# schematic.net
KiCad netlist of a schematic drawn in EasyEDA
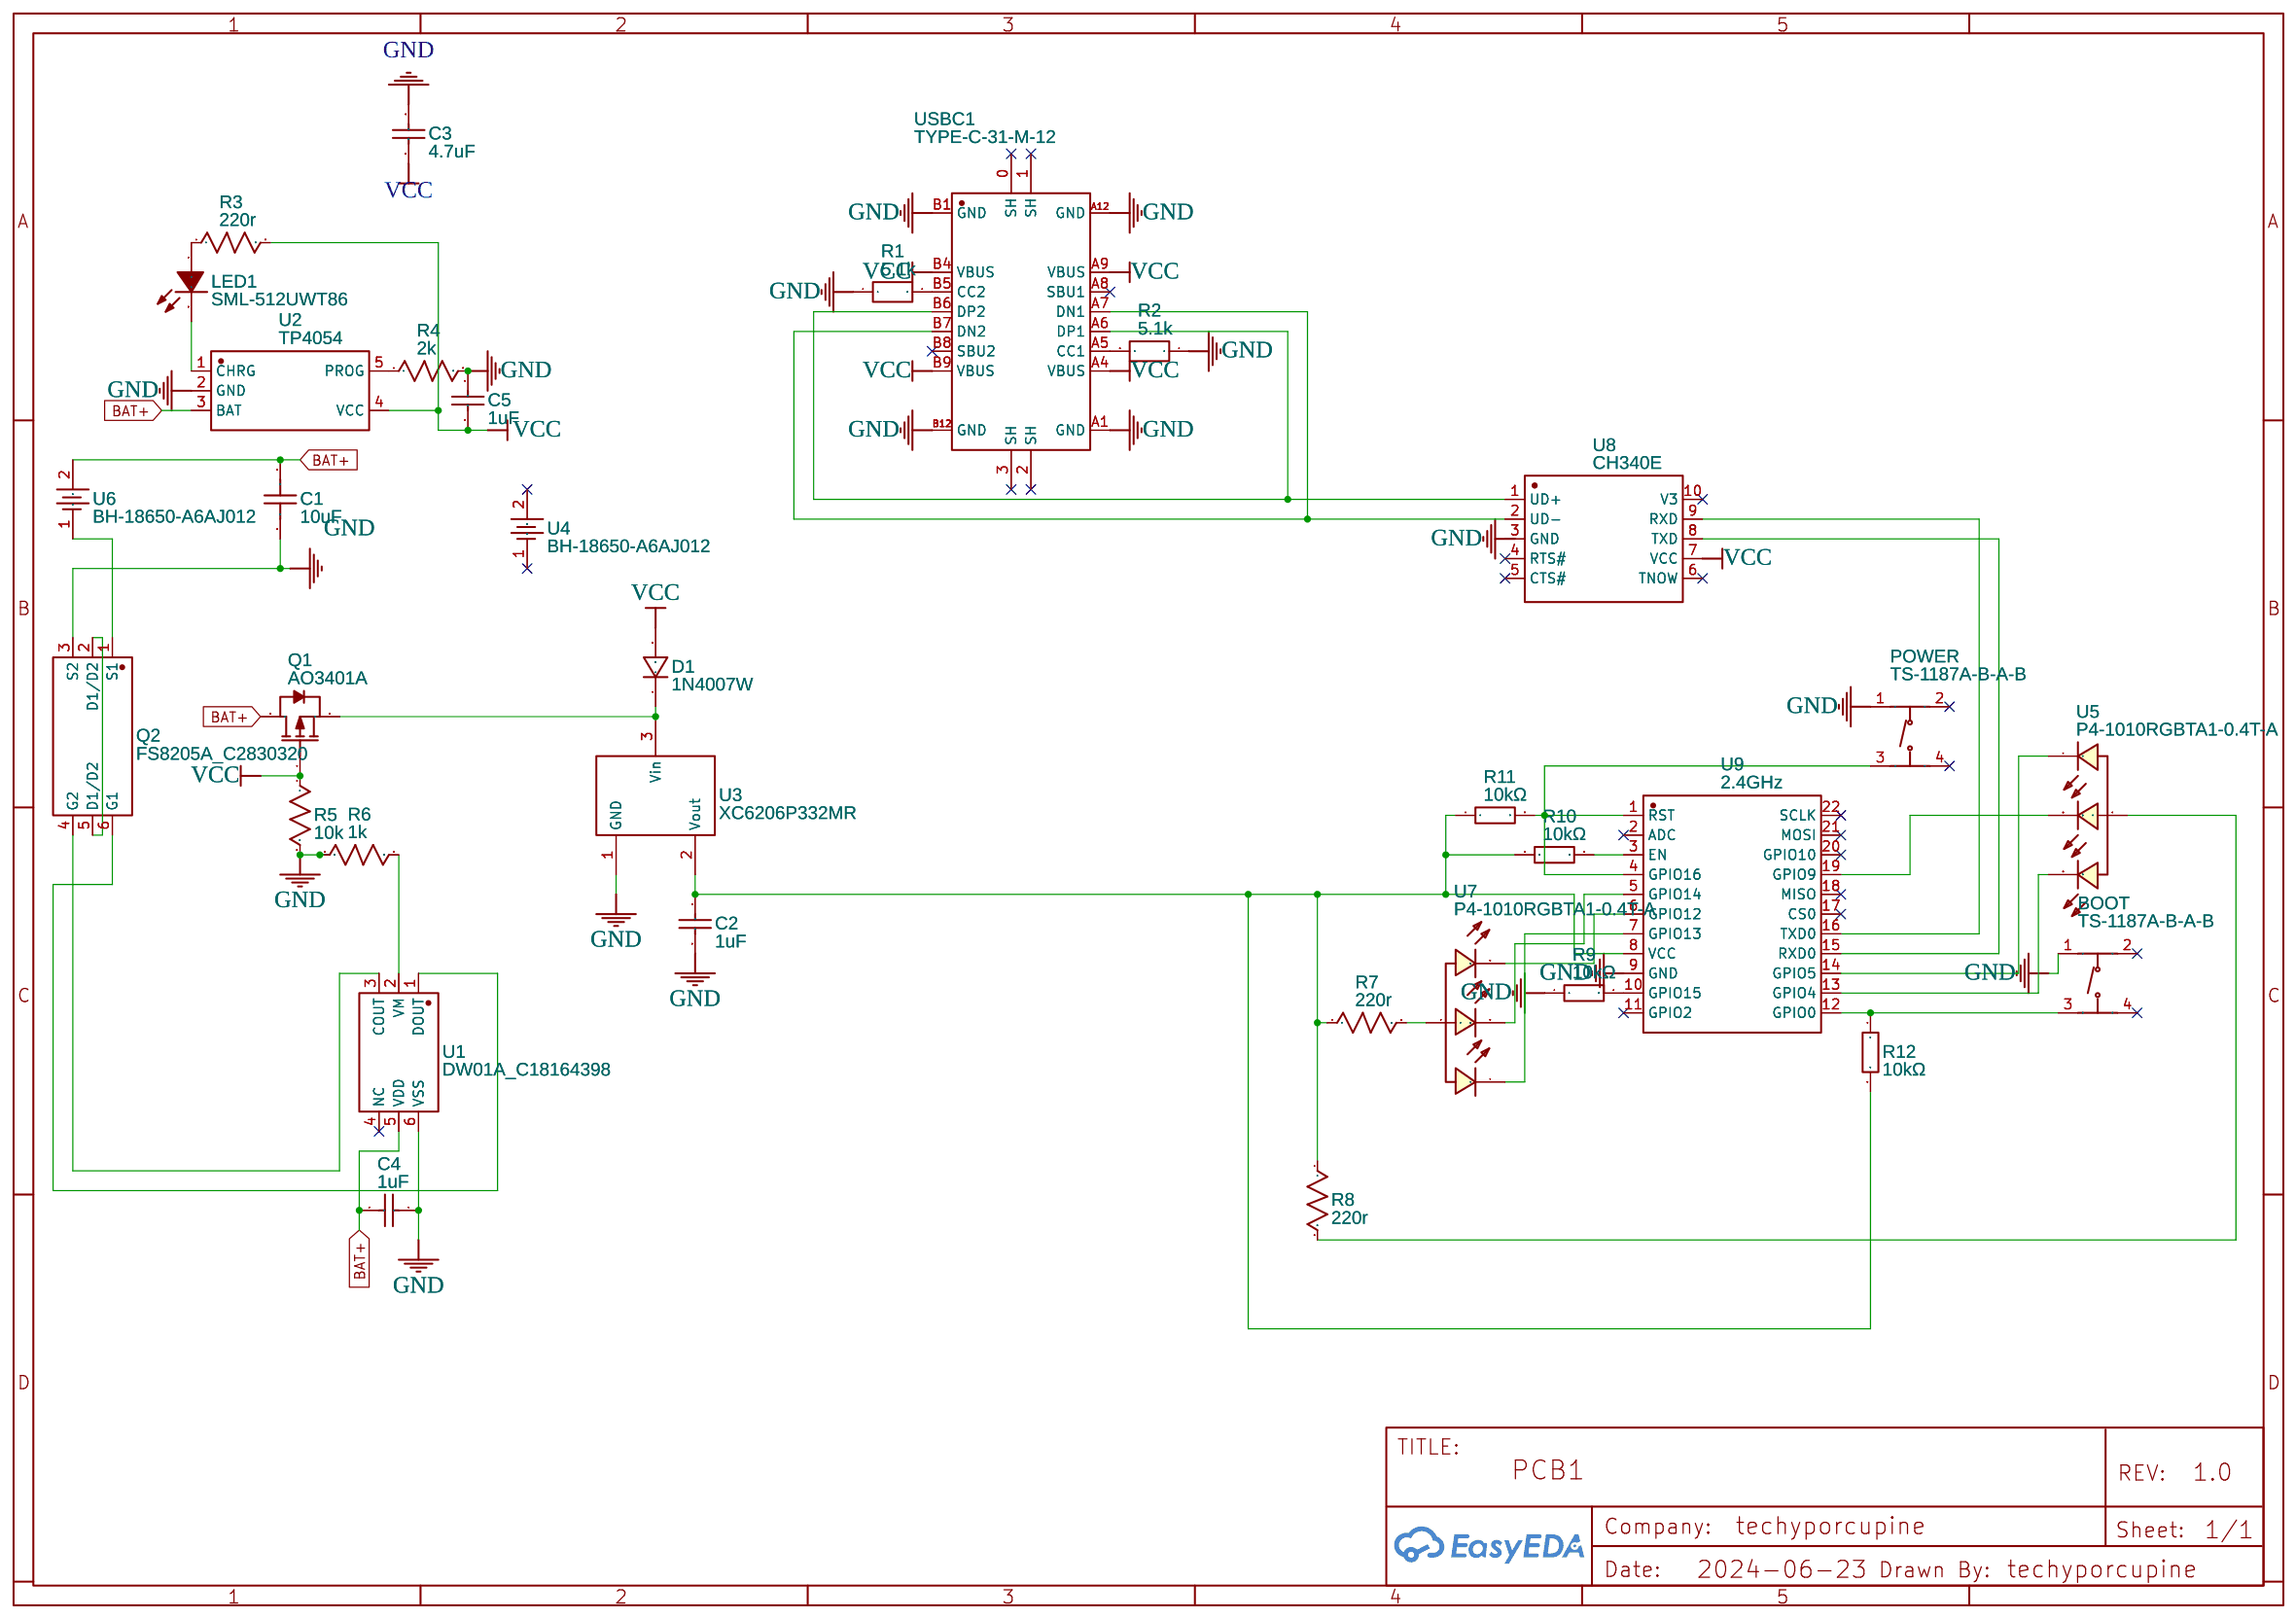
[diagram p0: schematic sheet]

(export (version "E")
  (design (tool "Eeschema 10.0.6"))
  (components
    (comp (ref "BOOT")
      (value "TS-1187A-B-A-B")
      (fields (field (name "Manufacturer") "XKB Connectivity(中国星坤)"))
      (libsource (lib "") (part "TS-1187A-B-A-B_1"))
    )
    (comp (ref "C1")
      (value "10uF")
      (fields
        (field (name "Manufacturer Part") "GRT21BC71E106KE13L")
        (field (name "Manufacturer") "muRata(村田)")
      )
      (libsource (lib "") (part "GRT21BC71E106KE13L"))
    )
    (comp (ref "C2")
      (value "1uF")
      (fields (field (name "Manufacturer Part") "0805F105M500NT") (field (name "Manufacturer") "FH(风华)"))
      (libsource (lib "") (part "0805F105M500NT"))
    )
    (comp (ref "C3")
      (value "4.7uF")
      (fields
        (field (name "Manufacturer Part") "CL21A475KAQNNNE")
        (field (name "Manufacturer") "SAMSUNG(三星)")
      )
      (libsource (lib "") (part "CL21A475KAQNNNE"))
    )
    (comp (ref "C4")
      (value "1uF")
      (fields (field (name "Manufacturer Part") "0805F105M500NT") (field (name "Manufacturer") "FH(风华)"))
      (libsource (lib "") (part "0805F105M500NT_1"))
    )
    (comp (ref "C5")
      (value "1uF")
      (fields (field (name "Manufacturer Part") "0805F105M500NT") (field (name "Manufacturer") "FH(风华)"))
      (libsource (lib "") (part "0805F105M500NT"))
    )
    (comp (ref "D1")
      (value "1N4007W")
      (fields (field (name "Manufacturer") "BLUE ROCKET"))
      (libsource (lib "") (part "1N4007W"))
    )
    (comp (ref "LED1")
      (value "SML-512UWT86")
      (fields (field (name "Manufacturer Part") "SML-D12M1WT86") (field (name "Manufacturer") "ROHM(罗姆)"))
      (libsource (lib "") (part "SML-512UWT86"))
    )
    (comp (ref "POWER")
      (value "TS-1187A-B-A-B")
      (fields (field (name "Manufacturer") "XKB Connectivity(中国星坤)"))
      (libsource (lib "") (part "TS-1187A-B-A-B"))
    )
    (comp (ref "Q1")
      (value "AO3401A")
      (fields (field (name "Manufacturer") "AOS"))
      (libsource (lib "") (part "AO3401A"))
    )
    (comp (ref "Q2")
      (value "FS8205A_C2830320")
      (fields (field (name "Manufacturer Part") "FS8205A") (field (name "Manufacturer") "TECH PUBLIC(台舟)"))
      (libsource (lib "") (part "FS8205A_C2830320"))
    )
    (comp (ref "R1")
      (value "5.1k")
      (fields (field (name "Manufacturer Part") "RTT025101FTH") (field (name "Manufacturer") "RALEC(旺诠)"))
      (libsource (lib "") (part "R_0603_EU_1"))
    )
    (comp (ref "R2")
      (value "5.1k")
      (fields (field (name "Manufacturer Part") "RTT025101FTH") (field (name "Manufacturer") "RALEC(旺诠)"))
      (libsource (lib "") (part "R_0603_EU"))
    )
    (comp (ref "R3")
      (value "220r")
      (fields
        (field (name "Manufacturer Part") "0603WAF2200T5E")
        (field (name "Manufacturer") "UNI-ROYAL(厚声)")
      )
      (libsource (lib "") (part "R_0603_US_1"))
    )
    (comp (ref "R4")
      (value "2k")
      (fields
        (field (name "Manufacturer Part") "0402WGF2001TCE")
        (field (name "Manufacturer") "UNI-ROYAL(厚声)")
      )
      (libsource (lib "") (part "R_0603_US_1"))
    )
    (comp (ref "R5")
      (value "10k")
      (fields (field (name "Manufacturer Part") "ARG02BTC1002") (field (name "Manufacturer") "Viking(光颉)"))
      (libsource (lib "") (part "R_0603_US"))
    )
    (comp (ref "R6")
      (value "1k")
      (fields
        (field (name "Manufacturer Part") "0805W8F1001T5E")
        (field (name "Manufacturer") "UNI-ROYAL(厚声)")
      )
      (libsource (lib "") (part "R_0603_US_1"))
    )
    (comp (ref "R7")
      (value "220r")
      (fields
        (field (name "Manufacturer Part") "0603WAF2200T5E")
        (field (name "Manufacturer") "UNI-ROYAL(厚声)")
      )
      (libsource (lib "") (part "R_0603_US_1"))
    )
    (comp (ref "R8")
      (value "220r")
      (fields
        (field (name "Manufacturer Part") "0603WAF2200T5E")
        (field (name "Manufacturer") "UNI-ROYAL(厚声)")
      )
      (libsource (lib "") (part "R_0603_US"))
    )
    (comp (ref "R9")
      (value "10kΩ")
      (fields
        (field (name "Manufacturer Part") "0603WAF1002T5E")
        (field (name "Manufacturer") "UNI-ROYAL(厚声)")
      )
      (libsource (lib "") (part "0603WAF1002T5E_1"))
    )
    (comp (ref "R10")
      (value "10kΩ")
      (fields
        (field (name "Manufacturer Part") "0603WAF1002T5E")
        (field (name "Manufacturer") "UNI-ROYAL(厚声)")
      )
      (libsource (lib "") (part "0603WAF1002T5E_1"))
    )
    (comp (ref "R11")
      (value "10kΩ")
      (fields
        (field (name "Manufacturer Part") "0603WAF1002T5E")
        (field (name "Manufacturer") "UNI-ROYAL(厚声)")
      )
      (libsource (lib "") (part "0603WAF1002T5E_1"))
    )
    (comp (ref "R12")
      (value "10kΩ")
      (fields
        (field (name "Manufacturer Part") "0603WAF1002T5E")
        (field (name "Manufacturer") "UNI-ROYAL(厚声)")
      )
      (libsource (lib "") (part "0603WAF1002T5E"))
    )
    (comp (ref "U1")
      (value "DW01A_C18164398")
      (fields (field (name "Manufacturer Part") "DW01A") (field (name "Manufacturer") "HL(富海微)"))
      (libsource (lib "") (part "DW01A_C18164398"))
    )
    (comp (ref "U2")
      (value "TP4054")
      (fields
        (field (name "Manufacturer Part") "TP4054-42-SOT25R")
        (field (name "Manufacturer") "TOPPOWER(南京拓微)")
      )
      (libsource (lib "") (part "TP4054"))
    )
    (comp (ref "U3")
      (value "XC6206P332MR")
      (fields (field (name "Manufacturer Part") "XC6206P332MR-G") (field (name "Manufacturer") "TOREX(特瑞仕)"))
      (libsource (lib "") (part "XC6206P332MR"))
    )
    (comp (ref "U4")
      (value "BH-18650-A6AJ012")
      (fields (field (name "Manufacturer") "MYOUNG(美阳)"))
      (libsource (lib "") (part "BH-18650-A6AJ012"))
    )
    (comp (ref "U5")
      (value "P4-1010RGBTA1-0.4T-A")
      (fields (field (name "Manufacturer") "TUOZHAN(拓展光电)"))
      (libsource (lib "") (part "P4-1010RGBTA1-0.4T-A"))
    )
    (comp (ref "U6")
      (value "BH-18650-A6AJ012")
      (fields (field (name "Manufacturer") "MYOUNG(美阳)"))
      (libsource (lib "") (part "BH-18650-A6AJ012"))
    )
    (comp (ref "U7")
      (value "P4-1010RGBTA1-0.4T-A")
      (fields (field (name "Manufacturer") "TUOZHAN(拓展光电)"))
      (libsource (lib "") (part "P4-1010RGBTA1-0.4T-A_1"))
    )
    (comp (ref "U8")
      (value "CH340E")
      (fields (field (name "Manufacturer") "WCH(南京沁恒)"))
      (libsource (lib "") (part "CH340E"))
    )
    (comp (ref "U9")
      (value "2.4GHz")
      (fields
        (field (name "Manufacturer Part") "ESP-12F(ESP8266MOD)")
        (field (name "Manufacturer") "Ai-Thinker(安信可)")
      )
      (libsource (lib "") (part "ESP-12F(ESP8266MOD)"))
    )
    (comp (ref "USBC1")
      (value "TYPE-C-31-M-12")
      (fields (field (name "Manufacturer") "韩国韩荣"))
      (libsource (lib "") (part "TYPE-C-31-M-12"))
    )
  )
  (nets
    (net (code "1") (name "BAT+") (class "Default")
      (node (ref "C1") (pin "2") (pinfunction "2_2") (pintype "unspecified"))
      (node (ref "C4") (pin "2") (pinfunction "2_2") (pintype "input"))
      (node (ref "Q1") (pin "3") (pinfunction "D_3") (pintype "unspecified"))
      (node (ref "U1") (pin "5") (pinfunction "VDD_5") (pintype "unspecified"))
      (node (ref "U2") (pin "3") (pinfunction "BAT_3") (pintype "unspecified"))
      (node (ref "U6") (pin "2") (pinfunction "2_2") (pintype "input"))
    )
    (net (code "2") (name "GND") (class "Default")
      (node (ref "BOOT") (pin "1") (pinfunction "A_1") (pintype "unspecified"))
      (node (ref "C1") (pin "1") (pinfunction "1_1") (pintype "unspecified"))
      (node (ref "C2") (pin "2") (pinfunction "2_2") (pintype "input"))
      (node (ref "C3") (pin "2") (pinfunction "2_2") (pintype "input"))
      (node (ref "C4") (pin "1") (pinfunction "1_1") (pintype "input"))
      (node (ref "C5") (pin "1") (pinfunction "1_1") (pintype "input"))
      (node (ref "POWER") (pin "1") (pinfunction "A_1") (pintype "unspecified"))
      (node (ref "Q2") (pin "3") (pinfunction "S2_3") (pintype "unspecified"))
      (node (ref "R1") (pin "1") (pinfunction "1_1") (pintype "unspecified"))
      (node (ref "R2") (pin "1") (pinfunction "1_1") (pintype "unspecified"))
      (node (ref "R4") (pin "2") (pinfunction "2_2") (pintype "unspecified"))
      (node (ref "R5") (pin "2") (pinfunction "2_2") (pintype "unspecified"))
      (node (ref "R6") (pin "1") (pinfunction "1_1") (pintype "unspecified"))
      (node (ref "R9") (pin "1") (pinfunction "1_1") (pintype "input"))
      (node (ref "U1") (pin "6") (pinfunction "VSS_6") (pintype "unspecified"))
      (node (ref "U2") (pin "2") (pinfunction "GND_2") (pintype "unspecified"))
      (node (ref "U3") (pin "1") (pinfunction "GND_1") (pintype "unspecified"))
      (node (ref "U8") (pin "3") (pinfunction "GND_3") (pintype "unspecified"))
      (node (ref "U9") (pin "9") (pinfunction "GND_9") (pintype "unspecified"))
      (node (ref "USBC1") (pin "A1") (pinfunction "GND_A1") (pintype "unspecified"))
      (node (ref "USBC1") (pin "A12") (pinfunction "GND_A12") (pintype "unspecified"))
      (node (ref "USBC1") (pin "B1") (pinfunction "GND_B1") (pintype "unspecified"))
      (node (ref "USBC1") (pin "B12") (pinfunction "GND_B12") (pintype "unspecified"))
    )
    (net (code "3") (name "Net-(BOOT-C)") (class "Default")
      (node (ref "BOOT") (pin "3") (pinfunction "C_3") (pintype "unspecified"))
      (node (ref "R12") (pin "1") (pinfunction "1_1") (pintype "input"))
      (node (ref "U9") (pin "12") (pinfunction "GPIO0_12") (pintype "unspecified"))
    )
    (net (code "4") (name "Net-(LED1-A)") (class "Default")
      (node (ref "LED1") (pin "1") (pinfunction "A_1") (pintype "unspecified"))
      (node (ref "R3") (pin "1") (pinfunction "1_1") (pintype "unspecified"))
    )
    (net (code "5") (name "Net-(LED1-K)") (class "Default")
      (node (ref "LED1") (pin "2") (pinfunction "K_2") (pintype "unspecified"))
      (node (ref "U2") (pin "1") (pinfunction "CHRG_1") (pintype "unspecified"))
    )
    (net (code "6") (name "Net-(POWER-C)") (class "Default")
      (node (ref "POWER") (pin "3") (pinfunction "C_3") (pintype "unspecified"))
      (node (ref "R11") (pin "2") (pinfunction "2_2") (pintype "input"))
      (node (ref "U9") (pin "1") (pinfunction "RST_1") (pintype "unspecified"))
      (node (ref "U9") (pin "4") (pinfunction "GPIO16_4") (pintype "unspecified"))
    )
    (net (code "7") (name "Net-(Q1-S)") (class "Default")
      (node (ref "D1") (pin "1") (pinfunction "1_1") (pintype "unspecified"))
      (node (ref "Q1") (pin "2") (pinfunction "S_2") (pintype "unspecified"))
      (node (ref "U3") (pin "3") (pinfunction "Vin_3") (pintype "unspecified"))
    )
    (net (code "8") (name "Net-(Q2-D1{slash}D2-Pad2)") (class "Default")
      (node (ref "Q2") (pin "2") (pinfunction "D1/D2_2") (pintype "unspecified"))
      (node (ref "Q2") (pin "5") (pinfunction "D1/D2_5") (pintype "unspecified"))
    )
    (net (code "9") (name "Net-(Q2-G1)") (class "Default")
      (node (ref "Q2") (pin "6") (pinfunction "G1_6") (pintype "unspecified"))
      (node (ref "U1") (pin "1") (pinfunction "DOUT_1") (pintype "unspecified"))
    )
    (net (code "10") (name "Net-(Q2-G2)") (class "Default")
      (node (ref "Q2") (pin "4") (pinfunction "G2_4") (pintype "unspecified"))
      (node (ref "U1") (pin "3") (pinfunction "COUT_3") (pintype "unspecified"))
    )
    (net (code "11") (name "Net-(Q2-S1)") (class "Default")
      (node (ref "Q2") (pin "1") (pinfunction "S1_1") (pintype "unspecified"))
      (node (ref "U6") (pin "1") (pinfunction "1_1") (pintype "input"))
    )
    (net (code "12") (name "Net-(R7-Pad2)") (class "Default")
      (node (ref "R7") (pin "2") (pinfunction "2_2") (pintype "unspecified"))
      (node (ref "U7") (pin "1") (pinfunction "1_1") (pintype "unspecified"))
    )
    (net (code "13") (name "Net-(R8-Pad2)") (class "Default")
      (node (ref "R8") (pin "2") (pinfunction "2_2") (pintype "unspecified"))
      (node (ref "U5") (pin "1") (pinfunction "1_1") (pintype "unspecified"))
    )
    (net (code "14") (name "Net-(U1-VM)") (class "Default")
      (node (ref "R6") (pin "2") (pinfunction "2_2") (pintype "unspecified"))
      (node (ref "U1") (pin "2") (pinfunction "VM_2") (pintype "unspecified"))
    )
    (net (code "15") (name "Net-(U2-PROG)") (class "Default")
      (node (ref "R4") (pin "1") (pinfunction "1_1") (pintype "unspecified"))
      (node (ref "U2") (pin "5") (pinfunction "PROG_5") (pintype "unspecified"))
    )
    (net (code "16") (name "Net-(U3-Vout)") (class "Default")
      (node (ref "C2") (pin "1") (pinfunction "1_1") (pintype "input"))
      (node (ref "R10") (pin "1") (pinfunction "1_1") (pintype "input"))
      (node (ref "R11") (pin "1") (pinfunction "1_1") (pintype "input"))
      (node (ref "R12") (pin "2") (pinfunction "2_2") (pintype "input"))
      (node (ref "R7") (pin "1") (pinfunction "1_1") (pintype "unspecified"))
      (node (ref "R8") (pin "1") (pinfunction "1_1") (pintype "unspecified"))
      (node (ref "U3") (pin "2") (pinfunction "Vout_2") (pintype "unspecified"))
      (node (ref "U9") (pin "8") (pinfunction "VCC_8") (pintype "unspecified"))
    )
    (net (code "17") (name "Net-(U8-RXD)") (class "Default")
      (node (ref "U8") (pin "9") (pinfunction "RXD_9") (pintype "unspecified"))
      (node (ref "U9") (pin "16") (pinfunction "TXD0_16") (pintype "unspecified"))
    )
    (net (code "18") (name "Net-(U8-TXD)") (class "Default")
      (node (ref "U8") (pin "8") (pinfunction "TXD_8") (pintype "unspecified"))
      (node (ref "U9") (pin "15") (pinfunction "RXD0_15") (pintype "unspecified"))
    )
    (net (code "19") (name "Net-(U8-UD+)") (class "Default")
      (node (ref "U8") (pin "1") (pinfunction "UD+_1") (pintype "unspecified"))
      (node (ref "USBC1") (pin "A6") (pinfunction "DP1_A6") (pintype "unspecified"))
      (node (ref "USBC1") (pin "B6") (pinfunction "DP2_B6") (pintype "unspecified"))
    )
    (net (code "20") (name "Net-(U8-UD-)") (class "Default")
      (node (ref "U8") (pin "2") (pinfunction "UD-_2") (pintype "unspecified"))
      (node (ref "USBC1") (pin "A7") (pinfunction "DN1_A7") (pintype "unspecified"))
      (node (ref "USBC1") (pin "B7") (pinfunction "DN2_B7") (pintype "unspecified"))
    )
    (net (code "21") (name "Net-(U9-EN)") (class "Default")
      (node (ref "R10") (pin "2") (pinfunction "2_2") (pintype "input"))
      (node (ref "U9") (pin "3") (pinfunction "EN_3") (pintype "unspecified"))
    )
    (net (code "22") (name "Net-(U9-GPIO4)") (class "Default")
      (node (ref "U5") (pin "2") (pinfunction "2_2") (pintype "unspecified"))
      (node (ref "U9") (pin "13") (pinfunction "GPIO4_13") (pintype "unspecified"))
    )
    (net (code "23") (name "Net-(U9-GPIO5)") (class "Default")
      (node (ref "U5") (pin "4") (pinfunction "4_4") (pintype "unspecified"))
      (node (ref "U9") (pin "14") (pinfunction "GPIO5_14") (pintype "unspecified"))
    )
    (net (code "24") (name "Net-(U9-GPIO9)") (class "Default")
      (node (ref "U5") (pin "3") (pinfunction "3_3") (pintype "unspecified"))
      (node (ref "U9") (pin "19") (pinfunction "GPIO9_19") (pintype "unspecified"))
    )
    (net (code "25") (name "Net-(U9-GPIO12)") (class "Default")
      (node (ref "U7") (pin "2") (pinfunction "2_2") (pintype "unspecified"))
      (node (ref "U9") (pin "6") (pinfunction "GPIO12_6") (pintype "unspecified"))
    )
    (net (code "26") (name "Net-(U9-GPIO13)") (class "Default")
      (node (ref "U7") (pin "4") (pinfunction "4_4") (pintype "unspecified"))
      (node (ref "U9") (pin "7") (pinfunction "GPIO13_7") (pintype "unspecified"))
    )
    (net (code "27") (name "Net-(U9-GPIO14)") (class "Default")
      (node (ref "U7") (pin "3") (pinfunction "3_3") (pintype "unspecified"))
      (node (ref "U9") (pin "5") (pinfunction "GPIO14_5") (pintype "unspecified"))
    )
    (net (code "28") (name "Net-(U9-GPIO15)") (class "Default")
      (node (ref "R9") (pin "2") (pinfunction "2_2") (pintype "input"))
      (node (ref "U9") (pin "10") (pinfunction "GPIO15_10") (pintype "unspecified"))
    )
    (net (code "29") (name "Net-(USBC1-CC1)") (class "Default")
      (node (ref "R2") (pin "2") (pinfunction "2_2") (pintype "unspecified"))
      (node (ref "USBC1") (pin "A5") (pinfunction "CC1_A5") (pintype "unspecified"))
    )
    (net (code "30") (name "Net-(USBC1-CC2)") (class "Default")
      (node (ref "R1") (pin "2") (pinfunction "2_2") (pintype "unspecified"))
      (node (ref "USBC1") (pin "B5") (pinfunction "CC2_B5") (pintype "unspecified"))
    )
    (net (code "31") (name "VCC") (class "Default")
      (node (ref "C3") (pin "1") (pinfunction "1_1") (pintype "input"))
      (node (ref "C5") (pin "2") (pinfunction "2_2") (pintype "input"))
      (node (ref "D1") (pin "2") (pinfunction "2_2") (pintype "unspecified"))
      (node (ref "Q1") (pin "1") (pinfunction "G_1") (pintype "unspecified"))
      (node (ref "R3") (pin "2") (pinfunction "2_2") (pintype "unspecified"))
      (node (ref "R5") (pin "1") (pinfunction "1_1") (pintype "unspecified"))
      (node (ref "U2") (pin "4") (pinfunction "VCC_4") (pintype "unspecified"))
      (node (ref "U8") (pin "7") (pinfunction "VCC_7") (pintype "unspecified"))
      (node (ref "USBC1") (pin "A4") (pinfunction "VBUS_A4") (pintype "unspecified"))
      (node (ref "USBC1") (pin "A9") (pinfunction "VBUS_A9") (pintype "unspecified"))
      (node (ref "USBC1") (pin "B4") (pinfunction "VBUS_B4") (pintype "unspecified"))
      (node (ref "USBC1") (pin "B9") (pinfunction "VBUS_B9") (pintype "unspecified"))
    )
    (net (code "32") (name "unconnected-(BOOT-B-Pad2)") (class "Default")
      (node (ref "BOOT") (pin "2") (pinfunction "B_2") (pintype "unspecified+no_connect"))
    )
    (net (code "33") (name "unconnected-(BOOT-D-Pad4)") (class "Default")
      (node (ref "BOOT") (pin "4") (pinfunction "D_4") (pintype "unspecified+no_connect"))
    )
    (net (code "34") (name "unconnected-(POWER-B-Pad2)") (class "Default")
      (node (ref "POWER") (pin "2") (pinfunction "B_2") (pintype "unspecified+no_connect"))
    )
    (net (code "35") (name "unconnected-(POWER-D-Pad4)") (class "Default")
      (node (ref "POWER") (pin "4") (pinfunction "D_4") (pintype "unspecified+no_connect"))
    )
    (net (code "36") (name "unconnected-(U1-NC-Pad4)") (class "Default")
      (node (ref "U1") (pin "4") (pinfunction "NC_4") (pintype "unspecified+no_connect"))
    )
    (net (code "37") (name "unconnected-(U4-Pad1)") (class "Default")
      (node (ref "U4") (pin "1") (pinfunction "1_1") (pintype "input+no_connect"))
    )
    (net (code "38") (name "unconnected-(U4-Pad2)") (class "Default")
      (node (ref "U4") (pin "2") (pinfunction "2_2") (pintype "input+no_connect"))
    )
    (net (code "39") (name "unconnected-(U8-CTS#-Pad5)") (class "Default")
      (node (ref "U8") (pin "5") (pinfunction "CTS#_5") (pintype "unspecified+no_connect"))
    )
    (net (code "40") (name "unconnected-(U8-RTS#-Pad4)") (class "Default")
      (node (ref "U8") (pin "4") (pinfunction "RTS#_4") (pintype "unspecified+no_connect"))
    )
    (net (code "41") (name "unconnected-(U8-TNOW-Pad6)") (class "Default")
      (node (ref "U8") (pin "6") (pinfunction "TNOW_6") (pintype "unspecified+no_connect"))
    )
    (net (code "42") (name "unconnected-(U8-V3-Pad10)") (class "Default")
      (node (ref "U8") (pin "10") (pinfunction "V3_10") (pintype "unspecified+no_connect"))
    )
    (net (code "43") (name "unconnected-(U9-ADC-Pad2)") (class "Default")
      (node (ref "U9") (pin "2") (pinfunction "ADC_2") (pintype "unspecified+no_connect"))
    )
    (net (code "44") (name "unconnected-(U9-CS0-Pad17)") (class "Default")
      (node (ref "U9") (pin "17") (pinfunction "CS0_17") (pintype "unspecified+no_connect"))
    )
    (net (code "45") (name "unconnected-(U9-GPIO2-Pad11)") (class "Default")
      (node (ref "U9") (pin "11") (pinfunction "GPIO2_11") (pintype "unspecified+no_connect"))
    )
    (net (code "46") (name "unconnected-(U9-GPIO10-Pad20)") (class "Default")
      (node (ref "U9") (pin "20") (pinfunction "GPIO10_20") (pintype "unspecified+no_connect"))
    )
    (net (code "47") (name "unconnected-(U9-MISO-Pad18)") (class "Default")
      (node (ref "U9") (pin "18") (pinfunction "MISO_18") (pintype "unspecified+no_connect"))
    )
    (net (code "48") (name "unconnected-(U9-MOSI-Pad21)") (class "Default")
      (node (ref "U9") (pin "21") (pinfunction "MOSI_21") (pintype "unspecified+no_connect"))
    )
    (net (code "49") (name "unconnected-(U9-SCLK-Pad22)") (class "Default")
      (node (ref "U9") (pin "22") (pinfunction "SCLK_22") (pintype "unspecified+no_connect"))
    )
    (net (code "50") (name "unconnected-(USBC1-SBU1-PadA8)") (class "Default")
      (node (ref "USBC1") (pin "A8") (pinfunction "SBU1_A8") (pintype "unspecified+no_connect"))
    )
    (net (code "51") (name "unconnected-(USBC1-SBU2-PadB8)") (class "Default")
      (node (ref "USBC1") (pin "B8") (pinfunction "SBU2_B8") (pintype "unspecified+no_connect"))
    )
    (net (code "52") (name "unconnected-(USBC1-SH-Pad0)") (class "Default")
      (node (ref "USBC1") (pin "0") (pinfunction "SH_0") (pintype "unspecified+no_connect"))
    )
    (net (code "53") (name "unconnected-(USBC1-SH-Pad1)") (class "Default")
      (node (ref "USBC1") (pin "1") (pinfunction "SH_1") (pintype "unspecified+no_connect"))
    )
    (net (code "54") (name "unconnected-(USBC1-SH-Pad2)") (class "Default")
      (node (ref "USBC1") (pin "2") (pinfunction "SH_2") (pintype "unspecified+no_connect"))
    )
    (net (code "55") (name "unconnected-(USBC1-SH-Pad3)") (class "Default")
      (node (ref "USBC1") (pin "3") (pinfunction "SH_3") (pintype "unspecified+no_connect"))
    )
  )
)
